# Oscilator.net
KiCad netlist of a schematic drawn in Altium Designer
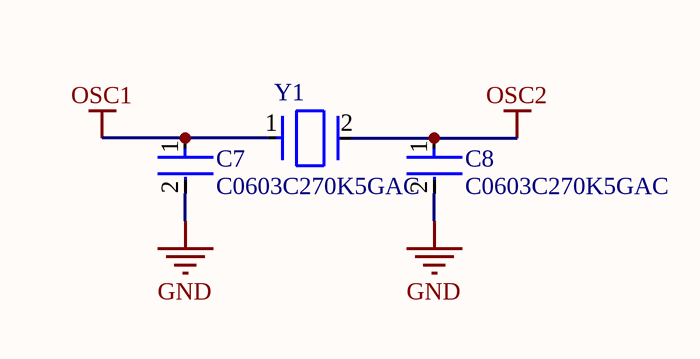
[diagram p0: Oscilator.SchDoc]

(export (version "E")
  (design (tool "Eeschema 10.0.6"))
  (components
    (comp (ref "C7")
      (value "C0603C270K5GAC")
      (footprint "FP-C0603C-CF-MFG")
      (description "C0603 27 pF C0G 30ppm/°C 10.00% 50 V")
      (fields
        (field (name "TOLERANCE") "0.1")
        (field (name "OCTOPART") "https://octopart.com/c0603c270k5gac-kemet-8089732")
      )
      (libsource (lib "Altium Content Vault") (part "b4654b650e69147ec39a6b967a45e02"))
    )
    (comp (ref "C8")
      (value "C0603C270K5GAC")
      (footprint "FP-C0603C-CF-MFG")
      (description "C0603 27 pF C0G 30ppm/°C 10.00% 50 V")
      (fields
        (field (name "TOLERANCE") "0.1")
        (field (name "OCTOPART") "https://octopart.com/c0603c270k5gac-kemet-8089732")
      )
      (libsource (lib "Altium Content Vault") (part "b4654b650e69147ec39a6b967a45e02"))
    )
    (comp (ref "Y1")
      (value "ABM3-8.000MHZ-D2Y-T")
      (footprint "FP-ABM3-MFG")
      (description "Crystal 8MHz ±20ppm 18pF SMD-2 5mm x 3.2mm")
      (fields (field (name "TOLERANCE") "20ppm"))
      (libsource (lib "Altium Content Vault") (part "c23a69dc6c9e2f18f2079038eb95dd1"))
    )
  )
  (nets
    (net (code "1") (name "GND") (class "Default")
      (node (ref "C7") (pin "2") (pinfunction "2_2") (pintype "passive"))
      (node (ref "C8") (pin "2") (pinfunction "2_2") (pintype "passive"))
    )
    (net (code "2") (name "OSC1") (class "Default")
      (node (ref "C7") (pin "1") (pinfunction "1_1") (pintype "passive"))
      (node (ref "Y1") (pin "1") (pinfunction "1_1") (pintype "passive"))
    )
    (net (code "3") (name "OSC2") (class "Default")
      (node (ref "C8") (pin "1") (pinfunction "1_1") (pintype "passive"))
      (node (ref "Y1") (pin "2") (pinfunction "2_2") (pintype "passive"))
    )
  )
)
